# Adapter-Board.net
KiCad netlist of a schematic drawn in EAGLE
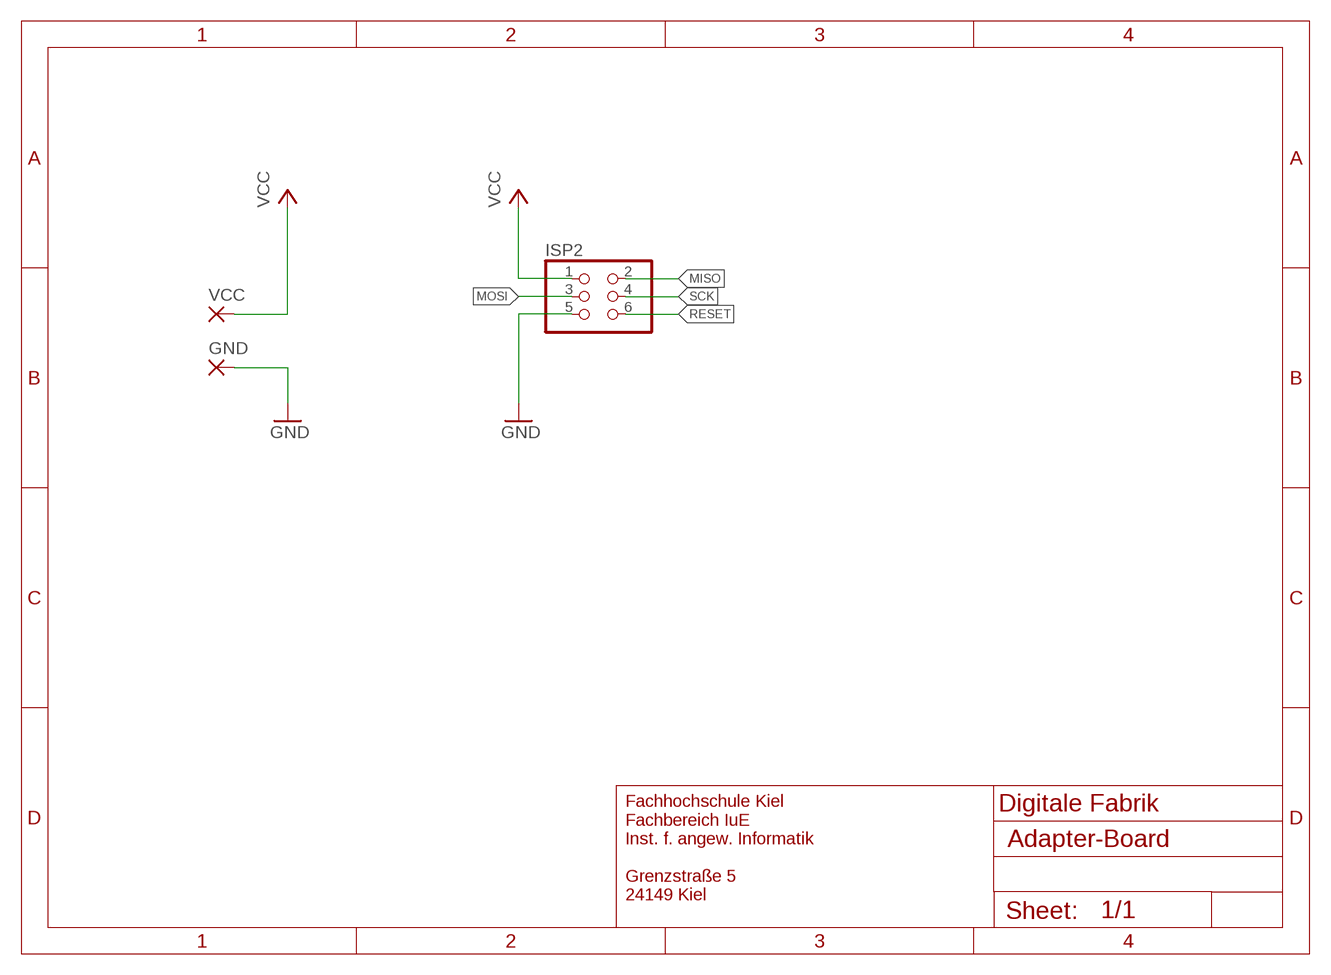
[diagram p0: schematic, sheet 1]

(export (version "E")
  (design (tool "Eeschema 10.0.6"))
  (components
    (comp (ref "GND")
      (value "SMD5")
      (footprint "eagle-import:SMD2,54-5,08")
      (libsource (lib "eagle-import") (part "SMD5"))
    )
    (comp (ref "ISP2")
      (value "PINHD-2X03_2.54-SMD")
      (footprint "eagle-import:2X03SMD")
      (libsource (lib "eagle-import") (part "PINHD-2X03_2.54-SMD"))
    )
    (comp (ref "VCC")
      (value "SMD5")
      (footprint "eagle-import:SMD2,54-5,08")
      (libsource (lib "eagle-import") (part "SMD5"))
    )
  )
  (nets
    (net (code "1") (name "GND") (class "Default")
      (node (ref "GND") (pin "1") (pinfunction "P_1") (pintype "passive"))
      (node (ref "ISP2") (pin "5") (pinfunction "5_5") (pintype "passive"))
    )
    (net (code "2") (name "MISO") (class "Default")
      (node (ref "ISP2") (pin "2") (pinfunction "2_2") (pintype "passive"))
    )
    (net (code "3") (name "MOSI") (class "Default")
      (node (ref "ISP2") (pin "3") (pinfunction "3_3") (pintype "passive"))
    )
    (net (code "4") (name "RESET") (class "Default")
      (node (ref "ISP2") (pin "6") (pinfunction "6_6") (pintype "passive"))
    )
    (net (code "5") (name "SCK") (class "Default")
      (node (ref "ISP2") (pin "4") (pinfunction "4_4") (pintype "passive"))
    )
    (net (code "6") (name "VCC") (class "Default")
      (node (ref "ISP2") (pin "1") (pinfunction "1_1") (pintype "passive"))
      (node (ref "VCC") (pin "1") (pinfunction "P_1") (pintype "passive"))
    )
  )
)
